# controller.net
KiCad netlist of a schematic drawn in EAGLE
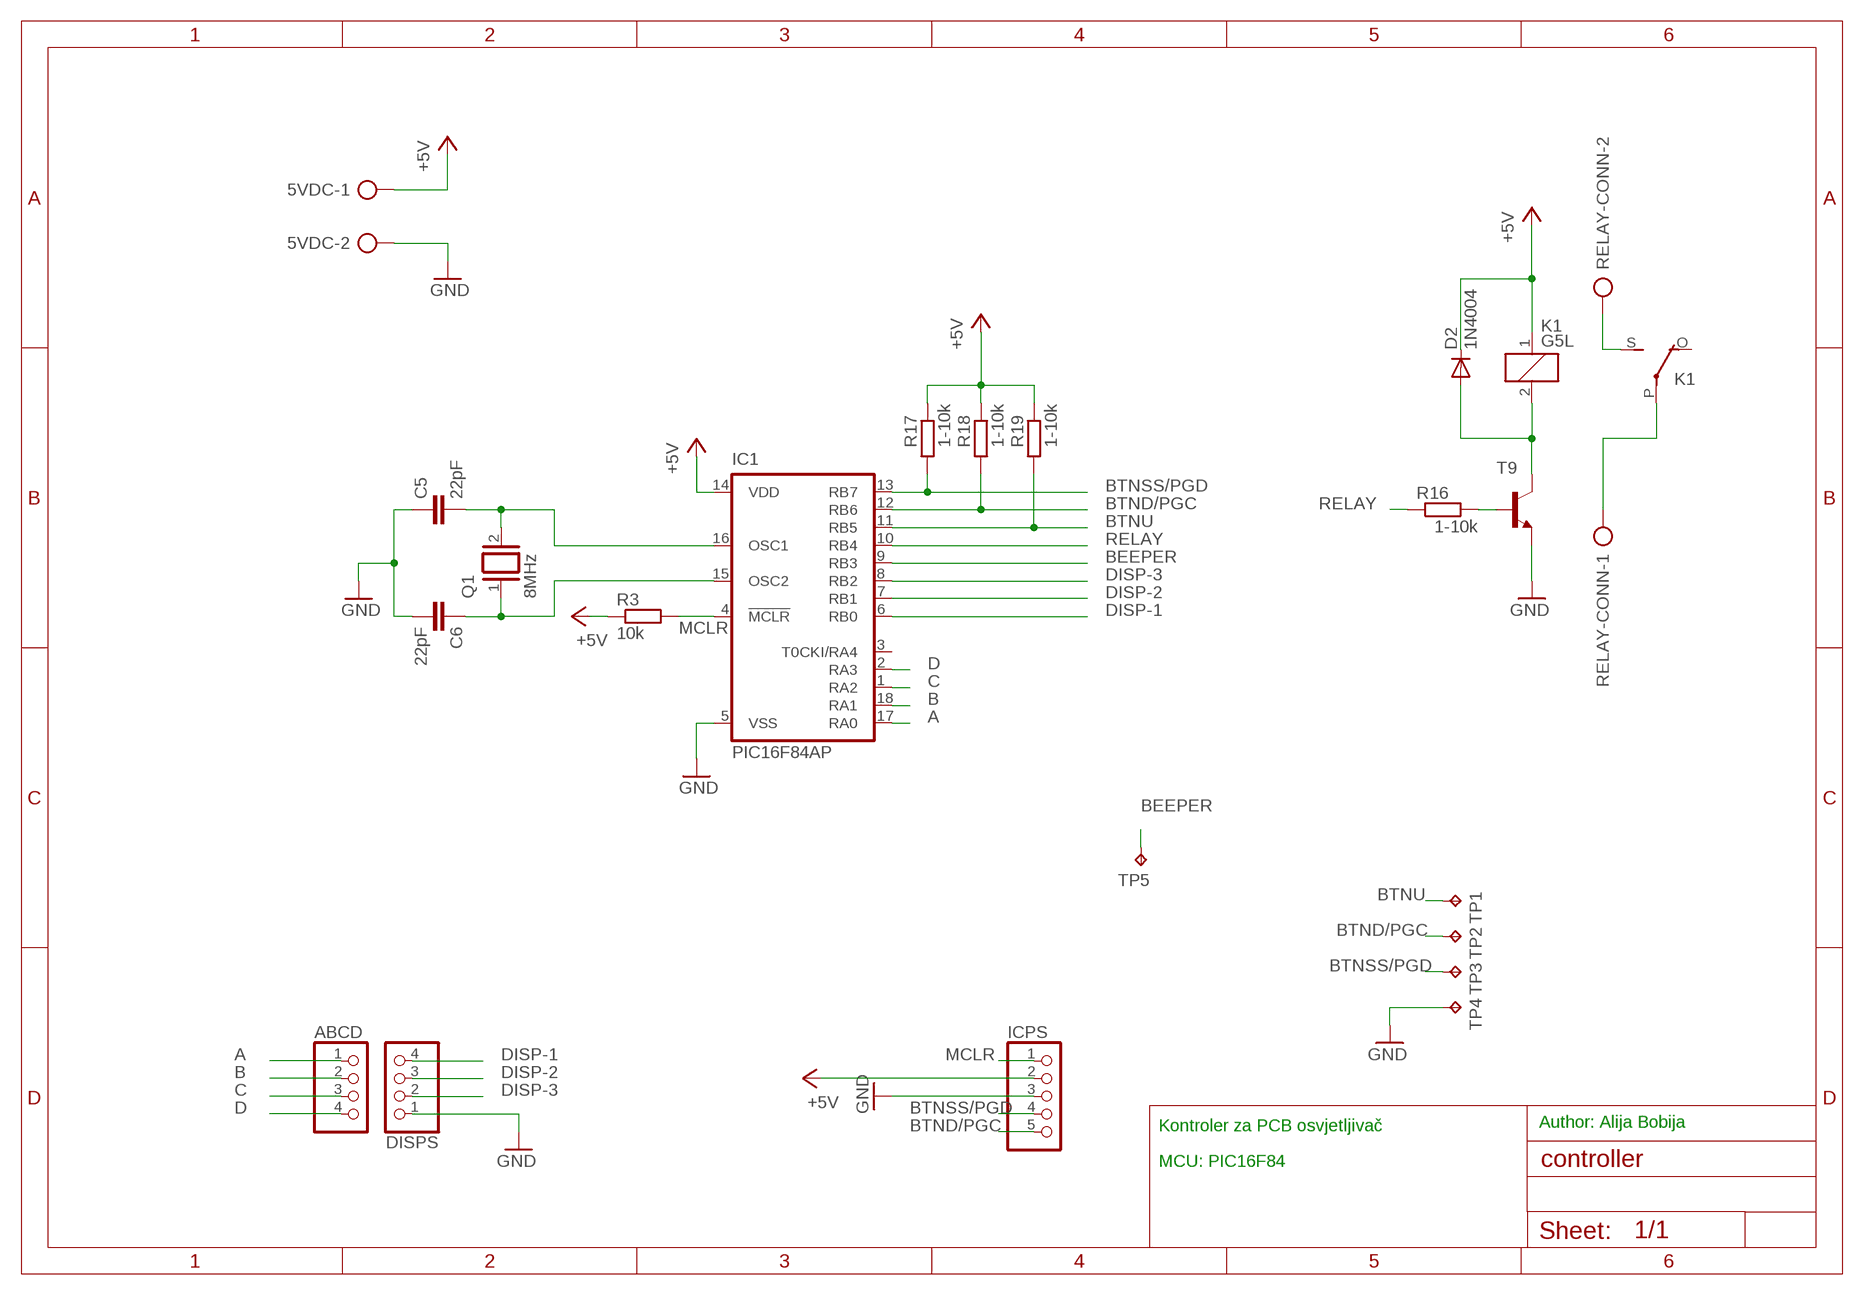
[diagram p0: schematic, sheet 1]

(export (version "E")
  (design (tool "Eeschema 10.0.6"))
  (components
    (comp (ref "5VDC")
      (value "AK500/2")
      (footprint "eagle-import:AK500_2")
      (libsource (lib "eagle-import") (part "AK500/2"))
    )
    (comp (ref "ABCD")
      (value "PINHD-1X4")
      (footprint "eagle-import:1X04")
      (libsource (lib "eagle-import") (part "PINHD-1X4"))
    )
    (comp (ref "C5")
      (value "22pF")
      (footprint "eagle-import:C025-024X044")
      (libsource (lib "eagle-import") (part "C-EU025-024X044"))
    )
    (comp (ref "C6")
      (value "22pF")
      (footprint "eagle-import:C025-024X044")
      (libsource (lib "eagle-import") (part "C-EU025-024X044"))
    )
    (comp (ref "D2")
      (value "1N4004")
      (footprint "eagle-import:DO41-10")
      (libsource (lib "eagle-import") (part "1N4004"))
    )
    (comp (ref "DISPS")
      (value "PINHD-1X4")
      (footprint "eagle-import:1X04")
      (libsource (lib "eagle-import") (part "PINHD-1X4"))
    )
    (comp (ref "IC1")
      (value "PIC16F84AP")
      (footprint "eagle-import:DIL18")
      (fields (field (name "MF") "MICROCHIP") (field (name "MPN") "PIC16F84A-04I/P"))
      (libsource (lib "eagle-import") (part "PIC16F8P4A"))
    )
    (comp (ref "ICPS")
      (value "PINHD-1X5/90")
      (footprint "eagle-import:1X05_90")
      (libsource (lib "eagle-import") (part "PINHD-1X5/90"))
    )
    (comp (ref "K1")
      (value "G5L")
      (footprint "eagle-import:G5LE")
      (libsource (lib "eagle-import") (part "G5L"))
    )
    (comp (ref "Q1")
      (value "8MHz")
      (footprint "eagle-import:QS")
      (libsource (lib "eagle-import") (part "XTAL/S"))
    )
    (comp (ref "R3")
      (value "10k")
      (footprint "eagle-import:0207_7")
      (libsource (lib "eagle-import") (part "R-EU_0207/7"))
    )
    (comp (ref "R16")
      (value "1-10k")
      (footprint "eagle-import:0207_7")
      (libsource (lib "eagle-import") (part "R-EU_0207/7"))
    )
    (comp (ref "R17")
      (value "1-10k")
      (footprint "eagle-import:0207_7")
      (libsource (lib "eagle-import") (part "R-EU_0207/7"))
    )
    (comp (ref "R18")
      (value "1-10k")
      (footprint "eagle-import:0207_7")
      (libsource (lib "eagle-import") (part "R-EU_0207/7"))
    )
    (comp (ref "R19")
      (value "1-10k")
      (footprint "eagle-import:0207_7")
      (libsource (lib "eagle-import") (part "R-EU_0207/7"))
    )
    (comp (ref "RELAY-CONN")
      (value "AK500/2")
      (footprint "eagle-import:AK500_2")
      (libsource (lib "eagle-import") (part "AK500/2"))
    )
    (comp (ref "T9")
      (value "-NPN-SOT23-EBC")
      (footprint "eagle-import:SOT23-EBC")
      (libsource (lib "eagle-import") (part "-NPN-SOT23-EBC"))
    )
    (comp (ref "TP1")
      (value "TPTP15SQ")
      (footprint "eagle-import:TP15SQ")
      (libsource (lib "eagle-import") (part "TPTP15SQ"))
    )
    (comp (ref "TP2")
      (value "TPTP15SQ")
      (footprint "eagle-import:TP15SQ")
      (libsource (lib "eagle-import") (part "TPTP15SQ"))
    )
    (comp (ref "TP3")
      (value "TPTP15SQ")
      (footprint "eagle-import:TP15SQ")
      (libsource (lib "eagle-import") (part "TPTP15SQ"))
    )
    (comp (ref "TP4")
      (value "TPTP15SQ")
      (footprint "eagle-import:TP15SQ")
      (libsource (lib "eagle-import") (part "TPTP15SQ"))
    )
    (comp (ref "TP5")
      (value "TPTP15SQ")
      (footprint "eagle-import:TP15SQ")
      (libsource (lib "eagle-import") (part "TPTP15SQ"))
    )
  )
  (nets
    (net (code "1") (name "+5V") (class "Default")
      (node (ref "5VDC") (pin "1") (pinfunction "KL_1") (pintype "passive"))
      (node (ref "D2") (pin "C") (pinfunction "C_C") (pintype "passive"))
      (node (ref "IC1") (pin "14") (pinfunction "VDD_14") (pintype "power_in"))
      (node (ref "ICPS") (pin "2") (pinfunction "2_2") (pintype "passive"))
      (node (ref "K1") (pin "1") (pinfunction "1_1") (pintype "passive"))
      (node (ref "R17") (pin "2") (pinfunction "2_2") (pintype "passive"))
      (node (ref "R18") (pin "2") (pinfunction "2_2") (pintype "passive"))
      (node (ref "R19") (pin "2") (pinfunction "2_2") (pintype "passive"))
      (node (ref "R3") (pin "1") (pinfunction "1_1") (pintype "passive"))
    )
    (net (code "2") (name "/A") (class "Default")
      (node (ref "ABCD") (pin "1") (pinfunction "1_1") (pintype "passive"))
      (node (ref "IC1") (pin "17") (pinfunction "RA0_17") (pintype "bidirectional"))
    )
    (net (code "3") (name "/B") (class "Default")
      (node (ref "ABCD") (pin "2") (pinfunction "2_2") (pintype "passive"))
      (node (ref "IC1") (pin "18") (pinfunction "RA1_18") (pintype "bidirectional"))
    )
    (net (code "4") (name "/BEEPER") (class "Default")
      (node (ref "IC1") (pin "9") (pinfunction "RB3_9") (pintype "bidirectional"))
      (node (ref "TP5") (pin "TP") (pinfunction "TP_TP") (pintype "input"))
    )
    (net (code "5") (name "/BTND{slash}PGC") (class "Default")
      (node (ref "IC1") (pin "12") (pinfunction "RB6_12") (pintype "bidirectional"))
      (node (ref "ICPS") (pin "5") (pinfunction "5_5") (pintype "passive"))
      (node (ref "R18") (pin "1") (pinfunction "1_1") (pintype "passive"))
      (node (ref "TP2") (pin "TP") (pinfunction "TP_TP") (pintype "input"))
    )
    (net (code "6") (name "/BTNSS{slash}PGD") (class "Default")
      (node (ref "IC1") (pin "13") (pinfunction "RB7_13") (pintype "bidirectional"))
      (node (ref "ICPS") (pin "4") (pinfunction "4_4") (pintype "passive"))
      (node (ref "R17") (pin "1") (pinfunction "1_1") (pintype "passive"))
      (node (ref "TP3") (pin "TP") (pinfunction "TP_TP") (pintype "input"))
    )
    (net (code "7") (name "/BTNU") (class "Default")
      (node (ref "IC1") (pin "11") (pinfunction "RB5_11") (pintype "bidirectional"))
      (node (ref "R19") (pin "1") (pinfunction "1_1") (pintype "passive"))
      (node (ref "TP1") (pin "TP") (pinfunction "TP_TP") (pintype "input"))
    )
    (net (code "8") (name "/C") (class "Default")
      (node (ref "ABCD") (pin "3") (pinfunction "3_3") (pintype "passive"))
      (node (ref "IC1") (pin "1") (pinfunction "RA2_1") (pintype "bidirectional"))
    )
    (net (code "9") (name "/D") (class "Default")
      (node (ref "ABCD") (pin "4") (pinfunction "4_4") (pintype "passive"))
      (node (ref "IC1") (pin "2") (pinfunction "RA3_2") (pintype "bidirectional"))
    )
    (net (code "10") (name "/DISP-1") (class "Default")
      (node (ref "DISPS") (pin "4") (pinfunction "4_4") (pintype "passive"))
      (node (ref "IC1") (pin "6") (pinfunction "RB0_6") (pintype "bidirectional"))
    )
    (net (code "11") (name "/DISP-2") (class "Default")
      (node (ref "DISPS") (pin "3") (pinfunction "3_3") (pintype "passive"))
      (node (ref "IC1") (pin "7") (pinfunction "RB1_7") (pintype "bidirectional"))
    )
    (net (code "12") (name "/DISP-3") (class "Default")
      (node (ref "DISPS") (pin "2") (pinfunction "2_2") (pintype "passive"))
      (node (ref "IC1") (pin "8") (pinfunction "RB2_8") (pintype "bidirectional"))
    )
    (net (code "13") (name "/MCLR") (class "Default")
      (node (ref "IC1") (pin "4") (pinfunction "~{MCLR}_4") (pintype "input"))
      (node (ref "ICPS") (pin "1") (pinfunction "1_1") (pintype "passive"))
      (node (ref "R3") (pin "2") (pinfunction "2_2") (pintype "passive"))
    )
    (net (code "14") (name "/RELAY") (class "Default")
      (node (ref "IC1") (pin "10") (pinfunction "RB4_10") (pintype "bidirectional"))
      (node (ref "R16") (pin "1") (pinfunction "1_1") (pintype "passive"))
    )
    (net (code "15") (name "GND") (class "Default")
      (node (ref "5VDC") (pin "2") (pinfunction "KL_2") (pintype "passive"))
      (node (ref "C5") (pin "1") (pinfunction "1_1") (pintype "passive"))
      (node (ref "C6") (pin "2") (pinfunction "2_2") (pintype "passive"))
      (node (ref "DISPS") (pin "1") (pinfunction "1_1") (pintype "passive"))
      (node (ref "IC1") (pin "5") (pinfunction "VSS_5") (pintype "power_in"))
      (node (ref "ICPS") (pin "3") (pinfunction "3_3") (pintype "passive"))
      (node (ref "T9") (pin "E") (pinfunction "E_E") (pintype "passive"))
      (node (ref "TP4") (pin "TP") (pinfunction "TP_TP") (pintype "input"))
    )
    (net (code "16") (name "Net-(D2-PadA)") (class "Default")
      (node (ref "D2") (pin "A") (pinfunction "A_A") (pintype "passive"))
      (node (ref "K1") (pin "2") (pinfunction "2_2") (pintype "passive"))
      (node (ref "T9") (pin "C") (pinfunction "C_C") (pintype "passive"))
    )
    (net (code "17") (name "Net-(IC1-OSC1)") (class "Default")
      (node (ref "C5") (pin "2") (pinfunction "2_2") (pintype "passive"))
      (node (ref "IC1") (pin "16") (pinfunction "OSC1_16") (pintype "input"))
      (node (ref "Q1") (pin "2") (pinfunction "2_2") (pintype "passive"))
    )
    (net (code "18") (name "Net-(IC1-OSC2)") (class "Default")
      (node (ref "C6") (pin "1") (pinfunction "1_1") (pintype "passive"))
      (node (ref "IC1") (pin "15") (pinfunction "OSC2_15") (pintype "output"))
      (node (ref "Q1") (pin "1") (pinfunction "1_1") (pintype "passive"))
    )
    (net (code "19") (name "Net-(R16-Pad2)") (class "Default")
      (node (ref "R16") (pin "2") (pinfunction "2_2") (pintype "passive"))
      (node (ref "T9") (pin "B") (pinfunction "B_B") (pintype "passive"))
    )
    (net (code "20") (name "Net-(RELAY-CONNA-KL)") (class "Default")
      (node (ref "K1") (pin "P") (pinfunction "P_P") (pintype "passive"))
      (node (ref "RELAY-CONN") (pin "1") (pinfunction "KL_1") (pintype "passive"))
    )
    (net (code "21") (name "Net-(RELAY-CONNB-KL)") (class "Default")
      (node (ref "K1") (pin "S") (pinfunction "S_S") (pintype "passive"))
      (node (ref "RELAY-CONN") (pin "2") (pinfunction "KL_2") (pintype "passive"))
    )
    (net (code "22") (name "unconnected-(IC1-T0CKI{slash}RA4-Pad3)") (class "Default")
      (node (ref "IC1") (pin "3") (pinfunction "T0CKI/RA4_3") (pintype "bidirectional"))
    )
    (net (code "23") (name "unconnected-(K1-PadO)") (class "Default")
      (node (ref "K1") (pin "O") (pinfunction "O_O") (pintype "passive"))
    )
  )
)
